# DAC.net
KiCad netlist of a schematic drawn in Altium Designer
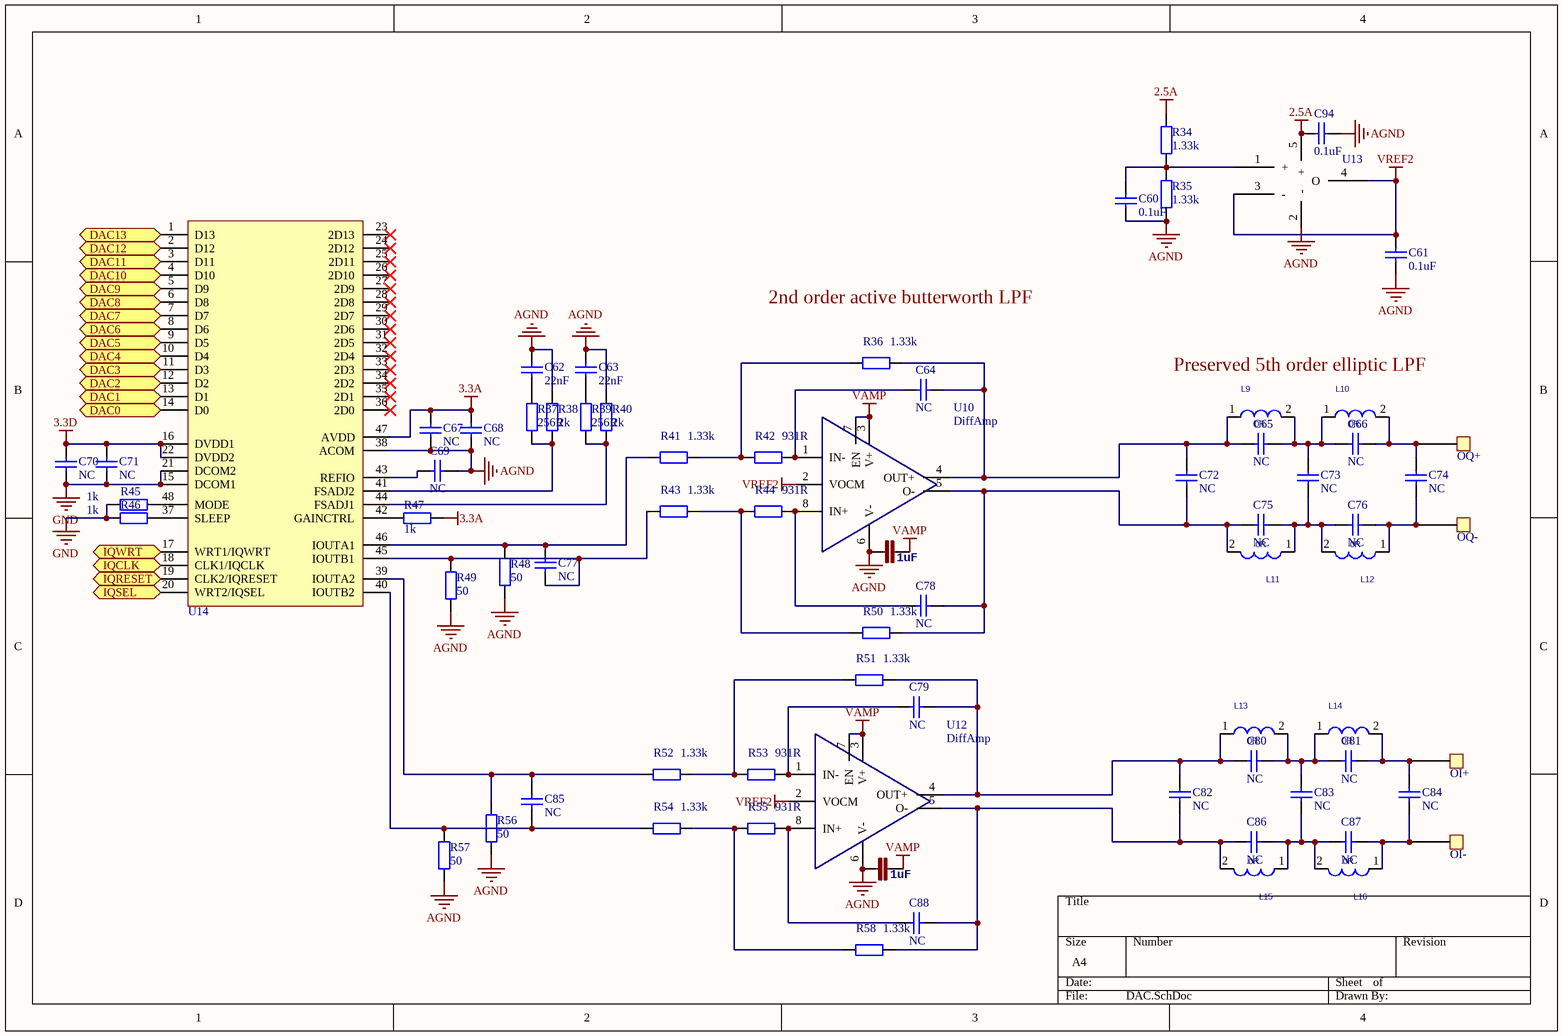
[diagram p0: DAC.SchDoc]

(export (version "E")
  (design (tool "Eeschema 10.0.6"))
  (components
    (comp (ref "C60")
      (value "0.1uF")
      (footprint "0402")
      (description "Capacitor")
      (fields (field (name "PUBLISHER") "Altium Limited"))
      (libsource (lib "RTC6705") (part "Cap"))
    )
    (comp (ref "C61")
      (value "0.1uF")
      (footprint "0402")
      (description "Capacitor")
      (fields (field (name "PUBLISHER") "Altium Limited"))
      (libsource (lib "RTC6705") (part "Cap"))
    )
    (comp (ref "C62")
      (value "22nF")
      (footprint "0402")
      (description "Capacitor")
      (fields (field (name "PUBLISHER") "Altium Limited"))
      (libsource (lib "RTC6705") (part "Cap"))
    )
    (comp (ref "C63")
      (value "22nF")
      (footprint "0402")
      (description "Capacitor")
      (fields (field (name "PUBLISHER") "Altium Limited"))
      (libsource (lib "RTC6705") (part "Cap"))
    )
    (comp (ref "C64")
      (value "NC")
      (footprint "0402")
      (description "Capacitor")
      (fields (field (name "PUBLISHER") "Altium Limited"))
      (libsource (lib "RTC6705") (part "Cap"))
    )
    (comp (ref "C65")
      (value "NC")
      (footprint "0402")
      (description "Capacitor")
      (fields (field (name "PUBLISHER") "Altium Limited"))
      (libsource (lib "RTC6705") (part "Cap"))
    )
    (comp (ref "C66")
      (value "NC")
      (footprint "0402")
      (description "Capacitor")
      (fields (field (name "PUBLISHER") "Altium Limited"))
      (libsource (lib "RTC6705") (part "Cap"))
    )
    (comp (ref "C67")
      (value "NC")
      (footprint "0603")
      (description "Capacitor")
      (fields (field (name "PUBLISHER") "Altium Limited"))
      (libsource (lib "RTC6705") (part "Cap"))
    )
    (comp (ref "C68")
      (value "NC")
      (footprint "0402")
      (description "Capacitor")
      (fields (field (name "PUBLISHER") "Altium Limited"))
      (libsource (lib "RTC6705") (part "Cap"))
    )
    (comp (ref "C69")
      (value "NC")
      (footprint "0603")
      (description "Capacitor")
      (fields (field (name "PUBLISHER") "Altium Limited"))
      (libsource (lib "RTC6705") (part "Cap"))
    )
    (comp (ref "C70")
      (value "NC")
      (footprint "0402")
      (description "Capacitor")
      (fields (field (name "PUBLISHER") "Altium Limited"))
      (libsource (lib "RTC6705") (part "Cap"))
    )
    (comp (ref "C71")
      (value "NC")
      (footprint "0402")
      (description "Capacitor")
      (fields (field (name "PUBLISHER") "Altium Limited"))
      (libsource (lib "RTC6705") (part "Cap"))
    )
    (comp (ref "C72")
      (value "NC")
      (footprint "0402")
      (description "Capacitor")
      (fields (field (name "PUBLISHER") "Altium Limited"))
      (libsource (lib "RTC6705") (part "Cap"))
    )
    (comp (ref "C73")
      (value "NC")
      (footprint "0402")
      (description "Capacitor")
      (fields (field (name "PUBLISHER") "Altium Limited"))
      (libsource (lib "RTC6705") (part "Cap"))
    )
    (comp (ref "C74")
      (value "NC")
      (footprint "0402")
      (description "Capacitor")
      (fields (field (name "PUBLISHER") "Altium Limited"))
      (libsource (lib "RTC6705") (part "Cap"))
    )
    (comp (ref "C75")
      (value "NC")
      (footprint "0402")
      (description "Capacitor")
      (fields (field (name "PUBLISHER") "Altium Limited"))
      (libsource (lib "RTC6705") (part "Cap"))
    )
    (comp (ref "C76")
      (value "NC")
      (footprint "0402")
      (description "Capacitor")
      (fields (field (name "PUBLISHER") "Altium Limited"))
      (libsource (lib "RTC6705") (part "Cap"))
    )
    (comp (ref "C77")
      (value "NC")
      (footprint "0402")
      (description "Capacitor")
      (fields (field (name "PUBLISHER") "Altium Limited"))
      (libsource (lib "RTC6705") (part "Cap"))
    )
    (comp (ref "C78")
      (value "NC")
      (footprint "0402")
      (description "Capacitor")
      (fields (field (name "PUBLISHER") "Altium Limited"))
      (libsource (lib "RTC6705") (part "Cap"))
    )
    (comp (ref "C79")
      (value "NC")
      (footprint "0402")
      (description "Capacitor")
      (fields (field (name "PUBLISHER") "Altium Limited"))
      (libsource (lib "RTC6705") (part "Cap"))
    )
    (comp (ref "C80")
      (value "NC")
      (footprint "0402")
      (description "Capacitor")
      (fields (field (name "PUBLISHER") "Altium Limited"))
      (libsource (lib "RTC6705") (part "Cap"))
    )
    (comp (ref "C81")
      (value "NC")
      (footprint "0402")
      (description "Capacitor")
      (fields (field (name "PUBLISHER") "Altium Limited"))
      (libsource (lib "RTC6705") (part "Cap"))
    )
    (comp (ref "C82")
      (value "NC")
      (footprint "0402")
      (description "Capacitor")
      (fields (field (name "PUBLISHER") "Altium Limited"))
      (libsource (lib "RTC6705") (part "Cap"))
    )
    (comp (ref "C83")
      (value "NC")
      (footprint "0402")
      (description "Capacitor")
      (fields (field (name "PUBLISHER") "Altium Limited"))
      (libsource (lib "RTC6705") (part "Cap"))
    )
    (comp (ref "C84")
      (value "NC")
      (footprint "0402")
      (description "Capacitor")
      (fields (field (name "PUBLISHER") "Altium Limited"))
      (libsource (lib "RTC6705") (part "Cap"))
    )
    (comp (ref "C85")
      (value "NC")
      (footprint "0402")
      (description "Capacitor")
      (fields (field (name "PUBLISHER") "Altium Limited"))
      (libsource (lib "RTC6705") (part "Cap"))
    )
    (comp (ref "C86")
      (value "NC")
      (footprint "0402")
      (description "Capacitor")
      (fields (field (name "PUBLISHER") "Altium Limited"))
      (libsource (lib "RTC6705") (part "Cap"))
    )
    (comp (ref "C87")
      (value "NC")
      (footprint "0402")
      (description "Capacitor")
      (fields (field (name "PUBLISHER") "Altium Limited"))
      (libsource (lib "RTC6705") (part "Cap"))
    )
    (comp (ref "C88")
      (value "NC")
      (footprint "0402")
      (description "Capacitor")
      (fields (field (name "PUBLISHER") "Altium Limited"))
      (libsource (lib "RTC6705") (part "Cap"))
    )
    (comp (ref "C91")
      (value "1uF")
      (footprint "0603")
      (description "<b>Capacitor</b>\nStandard 0603 ceramic capacitor, and 0.1\" leaded capacitor.")
      (fields (field (name "PARTNO") "CC0402ZRY5V7BB104"))
      (libsource (lib "pixhawk2") (part "CAP0402-CAP"))
    )
    (comp (ref "C92")
      (value "1uF")
      (footprint "0603")
      (description "<b>Capacitor</b>\nStandard 0603 ceramic capacitor, and 0.1\" leaded capacitor.")
      (fields (field (name "PARTNO") "CC0402ZRY5V7BB104"))
      (libsource (lib "pixhawk2") (part "CAP0402-CAP"))
    )
    (comp (ref "C94")
      (value "0.1uF")
      (footprint "0402")
      (description "Capacitor")
      (fields (field (name "PUBLISHER") "Altium Limited"))
      (libsource (lib "RTC6705") (part "Cap"))
    )
    (comp (ref "L9") (value "0R") (footprint "0402") (libsource (lib "*") (part "L/2.5*2.0")))
    (comp (ref "L10") (value "0R") (footprint "0402") (libsource (lib "*") (part "L/2.5*2.0")))
    (comp (ref "L11") (value "0R") (footprint "0402") (libsource (lib "*") (part "L/2.5*2.0")))
    (comp (ref "L12") (value "0R") (footprint "0402") (libsource (lib "*") (part "L/2.5*2.0")))
    (comp (ref "L13") (value "0R") (footprint "0402") (libsource (lib "*") (part "L/2.5*2.0")))
    (comp (ref "L14") (value "0R") (footprint "0402") (libsource (lib "*") (part "L/2.5*2.0")))
    (comp (ref "L15") (value "0R") (footprint "0402") (libsource (lib "*") (part "L/2.5*2.0")))
    (comp (ref "L16") (value "0R") (footprint "0402") (libsource (lib "*") (part "L/2.5*2.0")))
    (comp (ref "OI+") (value "TestPad") (footprint "TestPad - 1mm") (libsource (lib "sch") (part "TestPad")))
    (comp (ref "OI-") (value "TestPad") (footprint "TestPad - 1mm") (libsource (lib "sch") (part "TestPad")))
    (comp (ref "OQ+") (value "TestPad") (footprint "TestPad - 1mm") (libsource (lib "sch") (part "TestPad")))
    (comp (ref "OQ-") (value "TestPad") (footprint "TestPad - 1mm") (libsource (lib "sch") (part "TestPad")))
    (comp (ref "R34")
      (value "1.33k")
      (footprint "0402")
      (description "Resistor")
      (fields (field (name "PUBLISHER") "Altium Limited"))
      (libsource (lib "Miscellaneous Devices") (part "Res2"))
    )
    (comp (ref "R35")
      (value "1.33k")
      (footprint "0402")
      (description "Resistor")
      (fields (field (name "PUBLISHER") "Altium Limited"))
      (libsource (lib "Miscellaneous Devices") (part "Res2"))
    )
    (comp (ref "R36")
      (value "1.33k")
      (footprint "0402")
      (description "Resistor")
      (fields (field (name "PUBLISHER") "Altium Limited"))
      (libsource (lib "") (part "Res2_1"))
    )
    (comp (ref "R37")
      (value "256R")
      (footprint "0402")
      (description "Resistor")
      (fields (field (name "PUBLISHER") "Altium Limited"))
      (libsource (lib "") (part "Res2_2"))
    )
    (comp (ref "R38")
      (value "2k")
      (footprint "0402")
      (description "Resistor")
      (fields (field (name "PUBLISHER") "Altium Limited"))
      (libsource (lib "") (part "Res2_2"))
    )
    (comp (ref "R39")
      (value "256R")
      (footprint "0402")
      (description "Resistor")
      (fields (field (name "PUBLISHER") "Altium Limited"))
      (libsource (lib "") (part "Res2_2"))
    )
    (comp (ref "R40")
      (value "2k")
      (footprint "0402")
      (description "Resistor")
      (fields (field (name "PUBLISHER") "Altium Limited"))
      (libsource (lib "") (part "Res2_2"))
    )
    (comp (ref "R41")
      (value "1.33k")
      (footprint "0402")
      (description "Resistor")
      (fields (field (name "PUBLISHER") "Altium Limited"))
      (libsource (lib "") (part "Res2_1"))
    )
    (comp (ref "R42")
      (value "931R")
      (footprint "0402")
      (description "Resistor")
      (fields (field (name "PUBLISHER") "Altium Limited"))
      (libsource (lib "") (part "Res2_1"))
    )
    (comp (ref "R43")
      (value "1.33k")
      (footprint "0402")
      (description "Resistor")
      (fields (field (name "PUBLISHER") "Altium Limited"))
      (libsource (lib "") (part "Res2_1"))
    )
    (comp (ref "R44")
      (value "931R")
      (footprint "0402")
      (description "Resistor")
      (fields (field (name "PUBLISHER") "Altium Limited"))
      (libsource (lib "") (part "Res2_1"))
    )
    (comp (ref "R45")
      (value "1k")
      (footprint "0402")
      (description "Resistor")
      (fields (field (name "PUBLISHER") "Altium Limited"))
      (libsource (lib "") (part "Res2_1"))
    )
    (comp (ref "R46")
      (value "1k")
      (footprint "0402")
      (description "Resistor")
      (fields (field (name "PUBLISHER") "Altium Limited"))
      (libsource (lib "") (part "Res2_1"))
    )
    (comp (ref "R47")
      (value "1k")
      (footprint "0402")
      (description "Resistor")
      (fields (field (name "PUBLISHER") "Altium Limited"))
      (libsource (lib "") (part "Res2_3"))
    )
    (comp (ref "R48")
      (value "50")
      (footprint "0402")
      (description "Resistor")
      (fields (field (name "PUBLISHER") "Altium Limited"))
      (libsource (lib "") (part "Res2_2"))
    )
    (comp (ref "R49")
      (value "50")
      (footprint "0402")
      (description "Resistor")
      (fields (field (name "PUBLISHER") "Altium Limited"))
      (libsource (lib "Miscellaneous Devices") (part "Res2"))
    )
    (comp (ref "R50")
      (value "1.33k")
      (footprint "0402")
      (description "Resistor")
      (fields (field (name "PUBLISHER") "Altium Limited"))
      (libsource (lib "") (part "Res2_1"))
    )
    (comp (ref "R51")
      (value "1.33k")
      (footprint "0402")
      (description "Resistor")
      (fields (field (name "PUBLISHER") "Altium Limited"))
      (libsource (lib "") (part "Res2_1"))
    )
    (comp (ref "R52")
      (value "1.33k")
      (footprint "0402")
      (description "Resistor")
      (fields (field (name "PUBLISHER") "Altium Limited"))
      (libsource (lib "") (part "Res2_1"))
    )
    (comp (ref "R53")
      (value "931R")
      (footprint "0402")
      (description "Resistor")
      (fields (field (name "PUBLISHER") "Altium Limited"))
      (libsource (lib "") (part "Res2_1"))
    )
    (comp (ref "R54")
      (value "1.33k")
      (footprint "0402")
      (description "Resistor")
      (fields (field (name "PUBLISHER") "Altium Limited"))
      (libsource (lib "") (part "Res2_1"))
    )
    (comp (ref "R55")
      (value "931R")
      (footprint "0402")
      (description "Resistor")
      (fields (field (name "PUBLISHER") "Altium Limited"))
      (libsource (lib "") (part "Res2_1"))
    )
    (comp (ref "R56")
      (value "50")
      (footprint "0402")
      (description "Resistor")
      (fields (field (name "PUBLISHER") "Altium Limited"))
      (libsource (lib "") (part "Res2_2"))
    )
    (comp (ref "R57")
      (value "50")
      (footprint "0402")
      (description "Resistor")
      (fields (field (name "PUBLISHER") "Altium Limited"))
      (libsource (lib "Miscellaneous Devices") (part "Res2"))
    )
    (comp (ref "R58")
      (value "1.33k")
      (footprint "0402")
      (description "Resistor")
      (fields (field (name "PUBLISHER") "Altium Limited"))
      (libsource (lib "") (part "Res2_1"))
    )
    (comp (ref "U10") (value "DiffAmp") (footprint "MSOP8/VSSOP8") (libsource (lib "F4SDR") (part "DiffAmp")))
    (comp (ref "U12") (value "DiffAmp") (footprint "MSOP8/VSSOP8") (libsource (lib "F4SDR") (part "DiffAmp")))
    (comp (ref "U13") (value "OP-SOT23") (footprint "SOT23-5") (libsource (lib "sch") (part "OP-SOT23")))
    (comp (ref "U14") (value "AD9767") (footprint "AD9767") (libsource (lib "F4SDR") (part "AD9767")))
  )
  (nets
    (net (code "1") (name "/DAC0") (class "Default")
      (node (ref "U14") (pin "14") (pinfunction "D0_14") (pintype "passive"))
    )
    (net (code "2") (name "/DAC1") (class "Default")
      (node (ref "U14") (pin "13") (pinfunction "D1_13") (pintype "passive"))
    )
    (net (code "3") (name "/DAC2") (class "Default")
      (node (ref "U14") (pin "12") (pinfunction "D2_12") (pintype "passive"))
    )
    (net (code "4") (name "/DAC3") (class "Default")
      (node (ref "U14") (pin "11") (pinfunction "D3_11") (pintype "passive"))
    )
    (net (code "5") (name "/DAC4") (class "Default")
      (node (ref "U14") (pin "10") (pinfunction "D4_10") (pintype "passive"))
    )
    (net (code "6") (name "/DAC5") (class "Default")
      (node (ref "U14") (pin "9") (pinfunction "D5_9") (pintype "passive"))
    )
    (net (code "7") (name "/DAC6") (class "Default")
      (node (ref "U14") (pin "8") (pinfunction "D6_8") (pintype "passive"))
    )
    (net (code "8") (name "/DAC7") (class "Default")
      (node (ref "U14") (pin "7") (pinfunction "D7_7") (pintype "passive"))
    )
    (net (code "9") (name "/DAC8") (class "Default")
      (node (ref "U14") (pin "6") (pinfunction "D8_6") (pintype "passive"))
    )
    (net (code "10") (name "/DAC9") (class "Default")
      (node (ref "U14") (pin "5") (pinfunction "D9_5") (pintype "passive"))
    )
    (net (code "11") (name "/DAC10") (class "Default")
      (node (ref "U14") (pin "4") (pinfunction "D10_4") (pintype "passive"))
    )
    (net (code "12") (name "/DAC11") (class "Default")
      (node (ref "U14") (pin "3") (pinfunction "D11_3") (pintype "passive"))
    )
    (net (code "13") (name "/DAC12") (class "Default")
      (node (ref "U14") (pin "2") (pinfunction "D12_2") (pintype "passive"))
    )
    (net (code "14") (name "/DAC13") (class "Default")
      (node (ref "U14") (pin "1") (pinfunction "D13_1") (pintype "passive"))
    )
    (net (code "15") (name "/IQCLK") (class "Default")
      (node (ref "U14") (pin "18") (pinfunction "CLK1/IQCLK_18") (pintype "passive"))
    )
    (net (code "16") (name "/IQRESET") (class "Default")
      (node (ref "U14") (pin "19") (pinfunction "CLK2/IQRESET_19") (pintype "passive"))
    )
    (net (code "17") (name "/IQSEL") (class "Default")
      (node (ref "U14") (pin "20") (pinfunction "WRT2/IQSEL_20") (pintype "passive"))
    )
    (net (code "18") (name "/IQWRT") (class "Default")
      (node (ref "U14") (pin "17") (pinfunction "WRT1/IQWRT_17") (pintype "passive"))
    )
    (net (code "19") (name "2.5A") (class "Default")
      (node (ref "C94") (pin "1") (pinfunction "1_1") (pintype "passive"))
      (node (ref "R34") (pin "1") (pinfunction "1_1") (pintype "passive"))
      (node (ref "U13") (pin "5") (pinfunction "+_5") (pintype "passive"))
    )
    (net (code "20") (name "3.3A") (class "Default")
      (node (ref "C67") (pin "1") (pinfunction "1_1") (pintype "passive"))
      (node (ref "C68") (pin "1") (pinfunction "1_1") (pintype "passive"))
      (node (ref "R47") (pin "2") (pinfunction "2_2") (pintype "passive"))
      (node (ref "U14") (pin "47") (pinfunction "AVDD_47") (pintype "passive"))
    )
    (net (code "21") (name "3.3D") (class "Default")
      (node (ref "C70") (pin "1") (pinfunction "1_1") (pintype "passive"))
      (node (ref "C71") (pin "1") (pinfunction "1_1") (pintype "passive"))
      (node (ref "U14") (pin "16") (pinfunction "DVDD1_16") (pintype "passive"))
      (node (ref "U14") (pin "22") (pinfunction "DVDD2_22") (pintype "passive"))
    )
    (net (code "22") (name "AGND") (class "Default")
      (node (ref "C60") (pin "2") (pinfunction "2_2") (pintype "passive"))
      (node (ref "C61") (pin "2") (pinfunction "2_2") (pintype "passive"))
      (node (ref "C62") (pin "1") (pinfunction "1_1") (pintype "passive"))
      (node (ref "C63") (pin "1") (pinfunction "1_1") (pintype "passive"))
      (node (ref "C67") (pin "2") (pinfunction "2_2") (pintype "passive"))
      (node (ref "C68") (pin "2") (pinfunction "2_2") (pintype "passive"))
      (node (ref "C69") (pin "1") (pinfunction "1_1") (pintype "passive"))
      (node (ref "C91") (pin "2") (pinfunction "2_2") (pintype "passive"))
      (node (ref "C92") (pin "2") (pinfunction "2_2") (pintype "passive"))
      (node (ref "C94") (pin "2") (pinfunction "2_2") (pintype "passive"))
      (node (ref "R35") (pin "2") (pinfunction "2_2") (pintype "passive"))
      (node (ref "R38") (pin "2") (pinfunction "2_2") (pintype "passive"))
      (node (ref "R40") (pin "2") (pinfunction "2_2") (pintype "passive"))
      (node (ref "R48") (pin "1") (pinfunction "1_1") (pintype "passive"))
      (node (ref "R49") (pin "2") (pinfunction "2_2") (pintype "passive"))
      (node (ref "R56") (pin "1") (pinfunction "1_1") (pintype "passive"))
      (node (ref "R57") (pin "2") (pinfunction "2_2") (pintype "passive"))
      (node (ref "U10") (pin "6") (pinfunction "V-_6") (pintype "passive"))
      (node (ref "U12") (pin "6") (pinfunction "V-_6") (pintype "passive"))
      (node (ref "U13") (pin "2") (pinfunction "-_2") (pintype "passive"))
      (node (ref "U14") (pin "38") (pinfunction "ACOM_38") (pintype "passive"))
    )
    (net (code "23") (name "GND") (class "Default")
      (node (ref "C70") (pin "2") (pinfunction "2_2") (pintype "passive"))
      (node (ref "C71") (pin "2") (pinfunction "2_2") (pintype "passive"))
      (node (ref "R45") (pin "2") (pinfunction "2_2") (pintype "passive"))
      (node (ref "R46") (pin "2") (pinfunction "2_2") (pintype "passive"))
      (node (ref "U14") (pin "15") (pinfunction "DCOM1_15") (pintype "passive"))
      (node (ref "U14") (pin "21") (pinfunction "DCOM2_21") (pintype "passive"))
    )
    (net (code "24") (name "Net-(C60-Pad1)") (class "Default")
      (node (ref "C60") (pin "1") (pinfunction "1_1") (pintype "passive"))
      (node (ref "R34") (pin "2") (pinfunction "2_2") (pintype "passive"))
      (node (ref "R35") (pin "1") (pinfunction "1_1") (pintype "passive"))
      (node (ref "U13") (pin "1") (pinfunction "+_1") (pintype "passive"))
    )
    (net (code "25") (name "Net-(C62-Pad2)") (class "Default")
      (node (ref "C62") (pin "2") (pinfunction "2_2") (pintype "passive"))
      (node (ref "R37") (pin "2") (pinfunction "2_2") (pintype "passive"))
    )
    (net (code "26") (name "Net-(C63-Pad2)") (class "Default")
      (node (ref "C63") (pin "2") (pinfunction "2_2") (pintype "passive"))
      (node (ref "R39") (pin "2") (pinfunction "2_2") (pintype "passive"))
    )
    (net (code "27") (name "Net-(C65-Pad1)") (class "Default")
      (node (ref "C65") (pin "1") (pinfunction "1_1") (pintype "passive"))
      (node (ref "C66") (pin "2") (pinfunction "2_2") (pintype "passive"))
      (node (ref "C73") (pin "2") (pinfunction "2_2") (pintype "passive"))
      (node (ref "L10") (pin "1") (pinfunction "1_1") (pintype "passive"))
      (node (ref "L9") (pin "2") (pinfunction "2_2") (pintype "passive"))
    )
    (net (code "28") (name "Net-(C73-Pad1)") (class "Default")
      (node (ref "C73") (pin "1") (pinfunction "1_1") (pintype "passive"))
      (node (ref "C75") (pin "2") (pinfunction "2_2") (pintype "passive"))
      (node (ref "C76") (pin "1") (pinfunction "1_1") (pintype "passive"))
      (node (ref "L11") (pin "1") (pinfunction "1_1") (pintype "passive"))
      (node (ref "L12") (pin "2") (pinfunction "2_2") (pintype "passive"))
    )
    (net (code "29") (name "Net-(C80-Pad1)") (class "Default")
      (node (ref "C80") (pin "1") (pinfunction "1_1") (pintype "passive"))
      (node (ref "C81") (pin "2") (pinfunction "2_2") (pintype "passive"))
      (node (ref "C83") (pin "2") (pinfunction "2_2") (pintype "passive"))
      (node (ref "L13") (pin "2") (pinfunction "2_2") (pintype "passive"))
      (node (ref "L14") (pin "1") (pinfunction "1_1") (pintype "passive"))
    )
    (net (code "30") (name "Net-(C83-Pad1)") (class "Default")
      (node (ref "C83") (pin "1") (pinfunction "1_1") (pintype "passive"))
      (node (ref "C86") (pin "2") (pinfunction "2_2") (pintype "passive"))
      (node (ref "C87") (pin "1") (pinfunction "1_1") (pintype "passive"))
      (node (ref "L15") (pin "1") (pinfunction "1_1") (pintype "passive"))
      (node (ref "L16") (pin "2") (pinfunction "2_2") (pintype "passive"))
    )
    (net (code "31") (name "Net-(OI+-3)") (class "Default")
      (node (ref "C81") (pin "1") (pinfunction "1_1") (pintype "passive"))
      (node (ref "C84") (pin "2") (pinfunction "2_2") (pintype "passive"))
      (node (ref "L14") (pin "2") (pinfunction "2_2") (pintype "passive"))
      (node (ref "OI+") (pin "1") (pinfunction "3_1") (pintype "passive"))
    )
    (net (code "32") (name "Net-(OI--3)") (class "Default")
      (node (ref "C84") (pin "1") (pinfunction "1_1") (pintype "passive"))
      (node (ref "C87") (pin "2") (pinfunction "2_2") (pintype "passive"))
      (node (ref "L16") (pin "1") (pinfunction "1_1") (pintype "passive"))
      (node (ref "OI-") (pin "1") (pinfunction "3_1") (pintype "passive"))
    )
    (net (code "33") (name "Net-(OQ+-3)") (class "Default")
      (node (ref "C66") (pin "1") (pinfunction "1_1") (pintype "passive"))
      (node (ref "C74") (pin "2") (pinfunction "2_2") (pintype "passive"))
      (node (ref "L10") (pin "2") (pinfunction "2_2") (pintype "passive"))
      (node (ref "OQ+") (pin "1") (pinfunction "3_1") (pintype "passive"))
    )
    (net (code "34") (name "Net-(OQ--3)") (class "Default")
      (node (ref "C74") (pin "1") (pinfunction "1_1") (pintype "passive"))
      (node (ref "C76") (pin "2") (pinfunction "2_2") (pintype "passive"))
      (node (ref "L12") (pin "1") (pinfunction "1_1") (pintype "passive"))
      (node (ref "OQ-") (pin "1") (pinfunction "3_1") (pintype "passive"))
    )
    (net (code "35") (name "Net-(R36-Pad2)") (class "Default")
      (node (ref "R36") (pin "2") (pinfunction "2_2") (pintype "passive"))
      (node (ref "R41") (pin "1") (pinfunction "1_1") (pintype "passive"))
      (node (ref "R42") (pin "2") (pinfunction "2_2") (pintype "passive"))
    )
    (net (code "36") (name "Net-(R43-Pad1)") (class "Default")
      (node (ref "R43") (pin "1") (pinfunction "1_1") (pintype "passive"))
      (node (ref "R44") (pin "2") (pinfunction "2_2") (pintype "passive"))
      (node (ref "R50") (pin "2") (pinfunction "2_2") (pintype "passive"))
    )
    (net (code "37") (name "Net-(R51-Pad2)") (class "Default")
      (node (ref "R51") (pin "2") (pinfunction "2_2") (pintype "passive"))
      (node (ref "R52") (pin "1") (pinfunction "1_1") (pintype "passive"))
      (node (ref "R53") (pin "2") (pinfunction "2_2") (pintype "passive"))
    )
    (net (code "38") (name "Net-(R54-Pad1)") (class "Default")
      (node (ref "R54") (pin "1") (pinfunction "1_1") (pintype "passive"))
      (node (ref "R55") (pin "2") (pinfunction "2_2") (pintype "passive"))
      (node (ref "R58") (pin "2") (pinfunction "2_2") (pintype "passive"))
    )
    (net (code "39") (name "Net-(U10-IN+)") (class "Default")
      (node (ref "C78") (pin "2") (pinfunction "2_2") (pintype "passive"))
      (node (ref "R44") (pin "1") (pinfunction "1_1") (pintype "passive"))
      (node (ref "U10") (pin "8") (pinfunction "IN+_8") (pintype "passive"))
    )
    (net (code "40") (name "Net-(U10-IN-)") (class "Default")
      (node (ref "C64") (pin "2") (pinfunction "2_2") (pintype "passive"))
      (node (ref "R42") (pin "1") (pinfunction "1_1") (pintype "passive"))
      (node (ref "U10") (pin "1") (pinfunction "IN-_1") (pintype "passive"))
    )
    (net (code "41") (name "Net-(U10-O-)") (class "Default")
      (node (ref "C72") (pin "1") (pinfunction "1_1") (pintype "passive"))
      (node (ref "C75") (pin "1") (pinfunction "1_1") (pintype "passive"))
      (node (ref "C78") (pin "1") (pinfunction "1_1") (pintype "passive"))
      (node (ref "L11") (pin "2") (pinfunction "2_2") (pintype "passive"))
      (node (ref "R50") (pin "1") (pinfunction "1_1") (pintype "passive"))
      (node (ref "U10") (pin "5") (pinfunction "O-_5") (pintype "passive"))
    )
    (net (code "42") (name "Net-(U10-OUT+)") (class "Default")
      (node (ref "C64") (pin "1") (pinfunction "1_1") (pintype "passive"))
      (node (ref "C65") (pin "2") (pinfunction "2_2") (pintype "passive"))
      (node (ref "C72") (pin "2") (pinfunction "2_2") (pintype "passive"))
      (node (ref "L9") (pin "1") (pinfunction "1_1") (pintype "passive"))
      (node (ref "R36") (pin "1") (pinfunction "1_1") (pintype "passive"))
      (node (ref "U10") (pin "4") (pinfunction "OUT+_4") (pintype "passive"))
    )
    (net (code "43") (name "Net-(U12-IN+)") (class "Default")
      (node (ref "C88") (pin "2") (pinfunction "2_2") (pintype "passive"))
      (node (ref "R55") (pin "1") (pinfunction "1_1") (pintype "passive"))
      (node (ref "U12") (pin "8") (pinfunction "IN+_8") (pintype "passive"))
    )
    (net (code "44") (name "Net-(U12-IN-)") (class "Default")
      (node (ref "C79") (pin "2") (pinfunction "2_2") (pintype "passive"))
      (node (ref "R53") (pin "1") (pinfunction "1_1") (pintype "passive"))
      (node (ref "U12") (pin "1") (pinfunction "IN-_1") (pintype "passive"))
    )
    (net (code "45") (name "Net-(U12-O-)") (class "Default")
      (node (ref "C82") (pin "1") (pinfunction "1_1") (pintype "passive"))
      (node (ref "C86") (pin "1") (pinfunction "1_1") (pintype "passive"))
      (node (ref "C88") (pin "1") (pinfunction "1_1") (pintype "passive"))
      (node (ref "L15") (pin "2") (pinfunction "2_2") (pintype "passive"))
      (node (ref "R58") (pin "1") (pinfunction "1_1") (pintype "passive"))
      (node (ref "U12") (pin "5") (pinfunction "O-_5") (pintype "passive"))
    )
    (net (code "46") (name "Net-(U12-OUT+)") (class "Default")
      (node (ref "C79") (pin "1") (pinfunction "1_1") (pintype "passive"))
      (node (ref "C80") (pin "2") (pinfunction "2_2") (pintype "passive"))
      (node (ref "C82") (pin "2") (pinfunction "2_2") (pintype "passive"))
      (node (ref "L13") (pin "1") (pinfunction "1_1") (pintype "passive"))
      (node (ref "R51") (pin "1") (pinfunction "1_1") (pintype "passive"))
      (node (ref "U12") (pin "4") (pinfunction "OUT+_4") (pintype "passive"))
    )
    (net (code "47") (name "Net-(U14-FSADJ1)") (class "Default")
      (node (ref "R39") (pin "1") (pinfunction "1_1") (pintype "passive"))
      (node (ref "R40") (pin "1") (pinfunction "1_1") (pintype "passive"))
      (node (ref "U14") (pin "44") (pinfunction "FSADJ1_44") (pintype "passive"))
    )
    (net (code "48") (name "Net-(U14-FSADJ2)") (class "Default")
      (node (ref "R37") (pin "1") (pinfunction "1_1") (pintype "passive"))
      (node (ref "R38") (pin "1") (pinfunction "1_1") (pintype "passive"))
      (node (ref "U14") (pin "41") (pinfunction "FSADJ2_41") (pintype "passive"))
    )
    (net (code "49") (name "Net-(U14-GAINCTRL)") (class "Default")
      (node (ref "R47") (pin "1") (pinfunction "1_1") (pintype "passive"))
      (node (ref "U14") (pin "42") (pinfunction "GAINCTRL_42") (pintype "passive"))
    )
    (net (code "50") (name "Net-(U14-IOUTA1)") (class "Default")
      (node (ref "C77") (pin "1") (pinfunction "1_1") (pintype "passive"))
      (node (ref "R41") (pin "2") (pinfunction "2_2") (pintype "passive"))
      (node (ref "R48") (pin "2") (pinfunction "2_2") (pintype "passive"))
      (node (ref "U14") (pin "46") (pinfunction "IOUTA1_46") (pintype "passive"))
    )
    (net (code "51") (name "Net-(U14-IOUTA2)") (class "Default")
      (node (ref "C85") (pin "1") (pinfunction "1_1") (pintype "passive"))
      (node (ref "R52") (pin "2") (pinfunction "2_2") (pintype "passive"))
      (node (ref "R56") (pin "2") (pinfunction "2_2") (pintype "passive"))
      (node (ref "U14") (pin "39") (pinfunction "IOUTA2_39") (pintype "passive"))
    )
    (net (code "52") (name "Net-(U14-IOUTB1)") (class "Default")
      (node (ref "C77") (pin "2") (pinfunction "2_2") (pintype "passive"))
      (node (ref "R43") (pin "2") (pinfunction "2_2") (pintype "passive"))
      (node (ref "R49") (pin "1") (pinfunction "1_1") (pintype "passive"))
      (node (ref "U14") (pin "45") (pinfunction "IOUTB1_45") (pintype "passive"))
    )
    (net (code "53") (name "Net-(U14-IOUTB2)") (class "Default")
      (node (ref "C85") (pin "2") (pinfunction "2_2") (pintype "passive"))
      (node (ref "R54") (pin "2") (pinfunction "2_2") (pintype "passive"))
      (node (ref "R57") (pin "1") (pinfunction "1_1") (pintype "passive"))
      (node (ref "U14") (pin "40") (pinfunction "IOUTB2_40") (pintype "passive"))
    )
    (net (code "54") (name "Net-(U14-MODE)") (class "Default")
      (node (ref "R45") (pin "1") (pinfunction "1_1") (pintype "passive"))
      (node (ref "U14") (pin "48") (pinfunction "MODE_48") (pintype "passive"))
    )
    (net (code "55") (name "Net-(U14-REFIO)") (class "Default")
      (node (ref "C69") (pin "2") (pinfunction "2_2") (pintype "passive"))
      (node (ref "U14") (pin "43") (pinfunction "REFIO_43") (pintype "passive"))
    )
    (net (code "56") (name "Net-(U14-SLEEP)") (class "Default")
      (node (ref "R46") (pin "1") (pinfunction "1_1") (pintype "passive"))
      (node (ref "U14") (pin "37") (pinfunction "SLEEP_37") (pintype "passive"))
    )
    (net (code "57") (name "VAMP") (class "Default")
      (node (ref "C91") (pin "1") (pinfunction "1_1") (pintype "passive"))
      (node (ref "C92") (pin "1") (pinfunction "1_1") (pintype "passive"))
      (node (ref "U10") (pin "3") (pinfunction "V+_3") (pintype "passive"))
      (node (ref "U10") (pin "7") (pinfunction "EN_7") (pintype "passive"))
      (node (ref "U12") (pin "3") (pinfunction "V+_3") (pintype "passive"))
      (node (ref "U12") (pin "7") (pinfunction "EN_7") (pintype "passive"))
    )
    (net (code "58") (name "VREF2") (class "Default")
      (node (ref "C61") (pin "1") (pinfunction "1_1") (pintype "passive"))
      (node (ref "U10") (pin "2") (pinfunction "VOCM_2") (pintype "passive"))
      (node (ref "U12") (pin "2") (pinfunction "VOCM_2") (pintype "passive"))
      (node (ref "U13") (pin "3") (pinfunction "-_3") (pintype "passive"))
      (node (ref "U13") (pin "4") (pinfunction "O_4") (pintype "passive"))
    )
    (net (code "59") (name "unconnected-(U14-2D0-Pad36)") (class "Default")
      (node (ref "U14") (pin "36") (pinfunction "2D0_36") (pintype "passive+no_connect"))
    )
    (net (code "60") (name "unconnected-(U14-2D1-Pad35)") (class "Default")
      (node (ref "U14") (pin "35") (pinfunction "2D1_35") (pintype "passive+no_connect"))
    )
    (net (code "61") (name "unconnected-(U14-2D2-Pad34)") (class "Default")
      (node (ref "U14") (pin "34") (pinfunction "2D2_34") (pintype "passive+no_connect"))
    )
    (net (code "62") (name "unconnected-(U14-2D3-Pad33)") (class "Default")
      (node (ref "U14") (pin "33") (pinfunction "2D3_33") (pintype "passive+no_connect"))
    )
    (net (code "63") (name "unconnected-(U14-2D4-Pad32)") (class "Default")
      (node (ref "U14") (pin "32") (pinfunction "2D4_32") (pintype "passive+no_connect"))
    )
    (net (code "64") (name "unconnected-(U14-2D5-Pad31)") (class "Default")
      (node (ref "U14") (pin "31") (pinfunction "2D5_31") (pintype "passive+no_connect"))
    )
    (net (code "65") (name "unconnected-(U14-2D6-Pad30)") (class "Default")
      (node (ref "U14") (pin "30") (pinfunction "2D6_30") (pintype "passive+no_connect"))
    )
    (net (code "66") (name "unconnected-(U14-2D7-Pad29)") (class "Default")
      (node (ref "U14") (pin "29") (pinfunction "2D7_29") (pintype "passive+no_connect"))
    )
    (net (code "67") (name "unconnected-(U14-2D8-Pad28)") (class "Default")
      (node (ref "U14") (pin "28") (pinfunction "2D8_28") (pintype "passive+no_connect"))
    )
    (net (code "68") (name "unconnected-(U14-2D9-Pad27)") (class "Default")
      (node (ref "U14") (pin "27") (pinfunction "2D9_27") (pintype "passive+no_connect"))
    )
    (net (code "69") (name "unconnected-(U14-2D10-Pad26)") (class "Default")
      (node (ref "U14") (pin "26") (pinfunction "2D10_26") (pintype "passive+no_connect"))
    )
    (net (code "70") (name "unconnected-(U14-2D11-Pad25)") (class "Default")
      (node (ref "U14") (pin "25") (pinfunction "2D11_25") (pintype "passive+no_connect"))
    )
    (net (code "71") (name "unconnected-(U14-2D12-Pad24)") (class "Default")
      (node (ref "U14") (pin "24") (pinfunction "2D12_24") (pintype "passive+no_connect"))
    )
    (net (code "72") (name "unconnected-(U14-2D13-Pad23)") (class "Default")
      (node (ref "U14") (pin "23") (pinfunction "2D13_23") (pintype "passive+no_connect"))
    )
  )
)
